# PCB_Project.net
KiCad netlist of a schematic drawn in Altium Designer
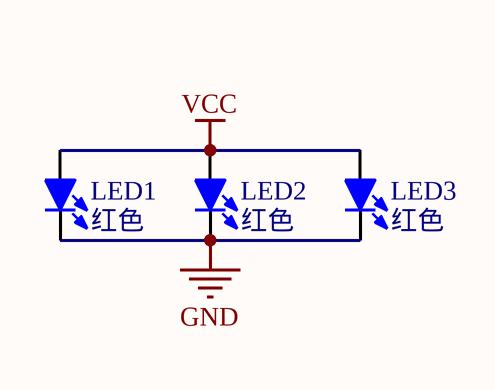
[diagram p0: PCB_Project.SchDoc]

(export (version "E")
  (design (tool "Eeschema 10.0.6"))
  (components
    (comp (ref "LED1")
      (value "红色")
      (footprint "LED 0805B")
      (description "贴片LED")
      (fields (field (name "版权归属") "源创客"))
      (libsource (lib "LED") (part "LED-SMD"))
    )
    (comp (ref "LED2")
      (value "红色")
      (footprint "LED 0805B")
      (description "贴片LED")
      (fields (field (name "版权归属") "源创客"))
      (libsource (lib "LED") (part "LED-SMD"))
    )
    (comp (ref "LED3")
      (value "红色")
      (footprint "LED 0805B")
      (description "贴片LED")
      (fields (field (name "版权归属") "源创客"))
      (libsource (lib "LED") (part "LED-SMD"))
    )
  )
  (nets
    (net (code "1") (name "GND") (class "Default")
      (node (ref "LED1") (pin "2") (pinfunction "K_2") (pintype "passive"))
      (node (ref "LED2") (pin "2") (pinfunction "K_2") (pintype "passive"))
      (node (ref "LED3") (pin "2") (pinfunction "K_2") (pintype "passive"))
    )
    (net (code "2") (name "VCC") (class "Default")
      (node (ref "LED1") (pin "1") (pinfunction "A_1") (pintype "passive"))
      (node (ref "LED2") (pin "1") (pinfunction "A_1") (pintype "passive"))
      (node (ref "LED3") (pin "1") (pinfunction "A_1") (pintype "passive"))
    )
  )
)
